# MCU.net
KiCad netlist of a schematic drawn in Altium Designer
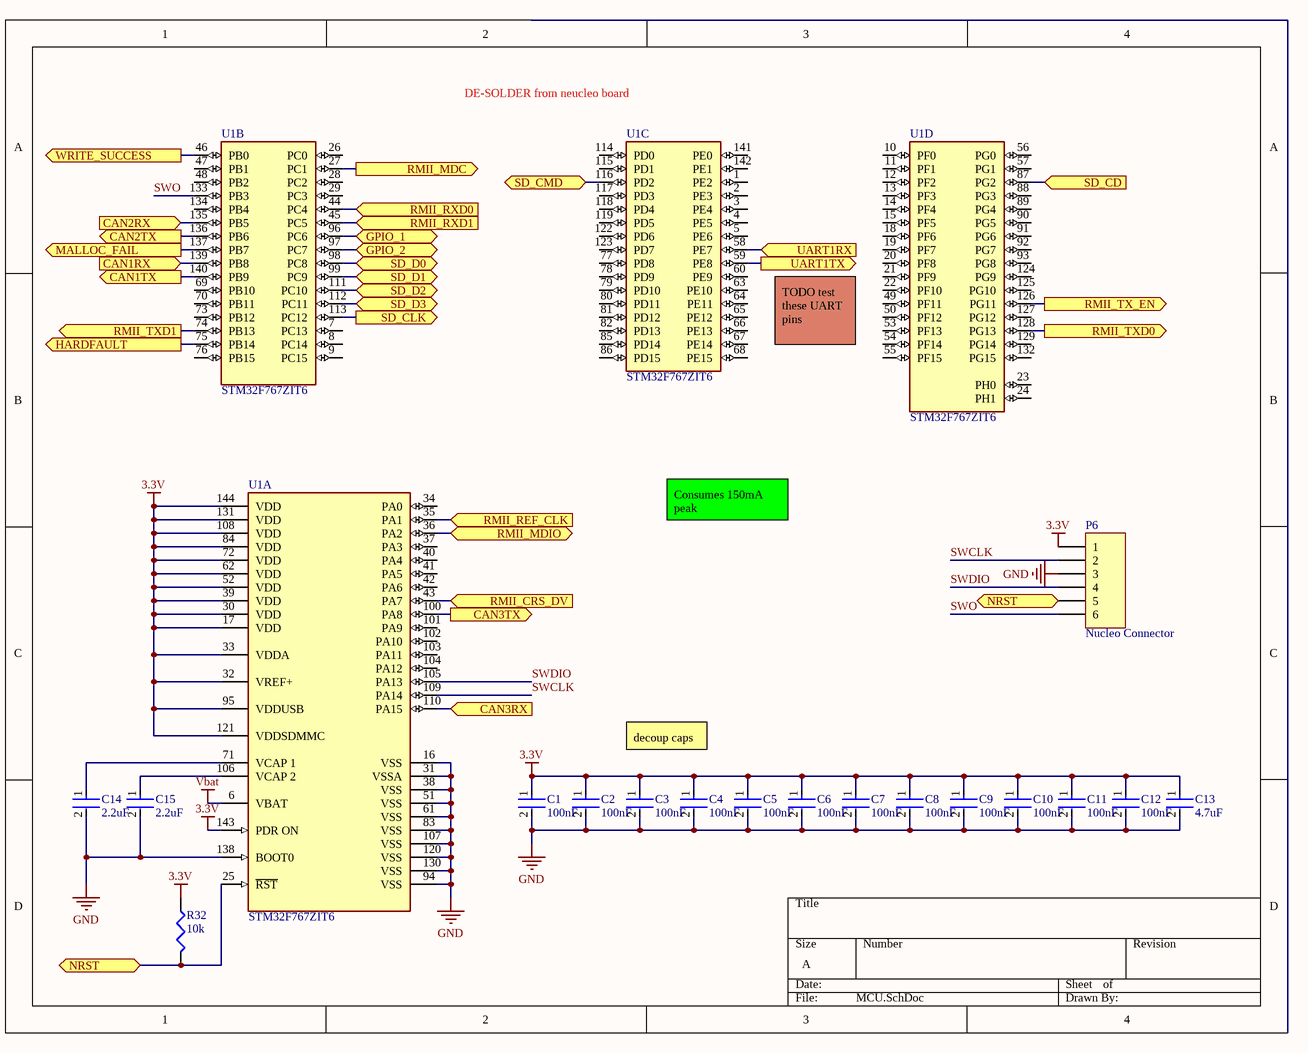
[diagram p0: MCU.SchDoc]

(export (version "E")
  (design (tool "Eeschema 10.0.6"))
  (components
    (comp (ref "C1")
      (value "100nF")
      (footprint "FP-C0603C-CF-MFG")
      (description "Any 0603 Cap is fine here")
      (fields (field (name "TOLERANCE") "0.1") (field (name "MANUFACTURER") "KEMET"))
      (libsource (lib "Altium Content Vault") (part "b4654b650e69147ec39a6b967a45e02"))
    )
    (comp (ref "C2")
      (value "100nF")
      (footprint "FP-C0603C-CF-MFG")
      (description "Any 0603 Cap is fine here")
      (fields (field (name "TOLERANCE") "0.1") (field (name "MANUFACTURER") "KEMET"))
      (libsource (lib "Altium Content Vault") (part "b4654b650e69147ec39a6b967a45e02"))
    )
    (comp (ref "C3")
      (value "100nF")
      (footprint "FP-C0603C-CF-MFG")
      (description "Any 0603 Cap is fine here")
      (fields (field (name "TOLERANCE") "0.1") (field (name "MANUFACTURER") "KEMET"))
      (libsource (lib "Altium Content Vault") (part "b4654b650e69147ec39a6b967a45e02"))
    )
    (comp (ref "C4")
      (value "100nF")
      (footprint "FP-C0603C-CF-MFG")
      (description "Any 0603 Cap is fine here")
      (fields (field (name "TOLERANCE") "0.1") (field (name "MANUFACTURER") "KEMET"))
      (libsource (lib "Altium Content Vault") (part "b4654b650e69147ec39a6b967a45e02"))
    )
    (comp (ref "C5")
      (value "100nF")
      (footprint "FP-C0603C-CF-MFG")
      (description "Any 0603 Cap is fine here")
      (fields (field (name "TOLERANCE") "0.1") (field (name "MANUFACTURER") "KEMET"))
      (libsource (lib "Altium Content Vault") (part "b4654b650e69147ec39a6b967a45e02"))
    )
    (comp (ref "C6")
      (value "100nF")
      (footprint "FP-C0603C-CF-MFG")
      (description "Any 0603 Cap is fine here")
      (fields (field (name "TOLERANCE") "0.1") (field (name "MANUFACTURER") "KEMET"))
      (libsource (lib "Altium Content Vault") (part "b4654b650e69147ec39a6b967a45e02"))
    )
    (comp (ref "C7")
      (value "100nF")
      (footprint "FP-C0603C-CF-MFG")
      (description "Any 0603 Cap is fine here")
      (fields (field (name "TOLERANCE") "0.1") (field (name "MANUFACTURER") "KEMET"))
      (libsource (lib "Altium Content Vault") (part "b4654b650e69147ec39a6b967a45e02"))
    )
    (comp (ref "C8")
      (value "100nF")
      (footprint "FP-C0603C-CF-MFG")
      (description "Any 0603 Cap is fine here")
      (fields (field (name "TOLERANCE") "0.1") (field (name "MANUFACTURER") "KEMET"))
      (libsource (lib "Altium Content Vault") (part "b4654b650e69147ec39a6b967a45e02"))
    )
    (comp (ref "C9")
      (value "100nF")
      (footprint "FP-C0603C-CF-MFG")
      (description "Any 0603 Cap is fine here")
      (fields (field (name "TOLERANCE") "0.1") (field (name "MANUFACTURER") "KEMET"))
      (libsource (lib "Altium Content Vault") (part "b4654b650e69147ec39a6b967a45e02"))
    )
    (comp (ref "C10")
      (value "100nF")
      (footprint "FP-C0603C-CF-MFG")
      (description "Any 0603 Cap is fine here")
      (fields (field (name "TOLERANCE") "0.1") (field (name "MANUFACTURER") "KEMET"))
      (libsource (lib "Altium Content Vault") (part "b4654b650e69147ec39a6b967a45e02"))
    )
    (comp (ref "C11")
      (value "100nF")
      (footprint "FP-C0603C-CF-MFG")
      (description "Any 0603 Cap is fine here")
      (fields (field (name "TOLERANCE") "0.1") (field (name "MANUFACTURER") "KEMET"))
      (libsource (lib "Altium Content Vault") (part "b4654b650e69147ec39a6b967a45e02"))
    )
    (comp (ref "C12")
      (value "100nF")
      (footprint "FP-C0603C-CF-MFG")
      (description "Any 0603 Cap is fine here")
      (fields (field (name "TOLERANCE") "0.1") (field (name "MANUFACTURER") "KEMET"))
      (libsource (lib "Altium Content Vault") (part "b4654b650e69147ec39a6b967a45e02"))
    )
    (comp (ref "C13")
      (value "4.7uF")
      (footprint "FP-C0603C-CF-MFG")
      (description "Any 0603 Cap is fine here")
      (fields (field (name "TOLERANCE") "0.1") (field (name "MANUFACTURER") "KEMET"))
      (libsource (lib "Altium Content Vault") (part "b4654b650e69147ec39a6b967a45e02"))
    )
    (comp (ref "C14")
      (value "2.2uF")
      (footprint "FP-C0603C-CF-MFG")
      (description "Any 0603 Cap is fine here")
      (fields (field (name "TOLERANCE") "0.1") (field (name "MANUFACTURER") "KEMET"))
      (libsource (lib "Altium Content Vault") (part "b4654b650e69147ec39a6b967a45e02"))
    )
    (comp (ref "C15")
      (value "2.2uF")
      (footprint "FP-C0603C-CF-MFG")
      (description "Any 0603 Cap is fine here")
      (fields (field (name "TOLERANCE") "0.1") (field (name "MANUFACTURER") "KEMET"))
      (libsource (lib "Altium Content Vault") (part "b4654b650e69147ec39a6b967a45e02"))
    )
    (comp (ref "P6")
      (value "Nucleo Connector")
      (footprint "HDR1X6")
      (description "Header, 6-Pin")
      (fields (field (name "PUBLISHER") "Altium Limited"))
      (libsource (lib "Miscellaneous Connectors") (part "Header 6"))
    )
    (comp (ref "R32")
      (value "10k")
      (footprint "J1-0603")
      (description "Resistor")
      (fields (field (name "PUBLISHER") "Altium Limited"))
      (libsource (lib "Miscellaneous Devices") (part "Res3"))
    )
    (comp (ref "U1")
      (value "STM32F767ZIT6")
      (footprint "FP-LQFP144-1A-MFG")
      (description "IC MCU 32BIT 2MB FLASH 144LQFP")
      (fields
        (field (name "OCTOPART") "https://octopart.com/stm32f767zit6-stmicroelectronics-70527068")
        (field (name "MANUFACTURER") "STMicroelectronics")
      )
      (libsource (lib "Altium Content Vault") (part "5045e889cff10565096e715f5715cbd"))
    )
  )
  (nets
    (net (code "1") (name "/CAN1RX") (class "Default")
      (node (ref "U1") (pin "139") (pinfunction "PB8_139") (pintype "bidirectional"))
    )
    (net (code "2") (name "/CAN1TX") (class "Default")
      (node (ref "U1") (pin "140") (pinfunction "PB9_140") (pintype "bidirectional"))
    )
    (net (code "3") (name "/CAN2RX") (class "Default")
      (node (ref "U1") (pin "135") (pinfunction "PB5_135") (pintype "bidirectional"))
    )
    (net (code "4") (name "/CAN2TX") (class "Default")
      (node (ref "U1") (pin "136") (pinfunction "PB6_136") (pintype "bidirectional"))
    )
    (net (code "5") (name "/CAN3RX") (class "Default")
      (node (ref "U1") (pin "110") (pinfunction "PA15_110") (pintype "bidirectional"))
    )
    (net (code "6") (name "/CAN3TX") (class "Default")
      (node (ref "U1") (pin "100") (pinfunction "PA8_100") (pintype "bidirectional"))
    )
    (net (code "7") (name "/GPIO_1") (class "Default")
      (node (ref "U1") (pin "96") (pinfunction "PC6_96") (pintype "bidirectional"))
    )
    (net (code "8") (name "/GPIO_2") (class "Default")
      (node (ref "U1") (pin "97") (pinfunction "PC7_97") (pintype "bidirectional"))
    )
    (net (code "9") (name "/HARDFAULT") (class "Default")
      (node (ref "U1") (pin "75") (pinfunction "PB14_75") (pintype "bidirectional"))
    )
    (net (code "10") (name "/MALLOC_FAIL") (class "Default")
      (node (ref "U1") (pin "137") (pinfunction "PB7_137") (pintype "bidirectional"))
    )
    (net (code "11") (name "/NRST") (class "Default")
      (node (ref "P6") (pin "5") (pinfunction "5_5") (pintype "passive"))
      (node (ref "R32") (pin "2") (pinfunction "2_2") (pintype "passive"))
      (node (ref "U1") (pin "25") (pinfunction "~{RST}_25") (pintype "input"))
    )
    (net (code "12") (name "/RMII_CRS_DV") (class "Default")
      (node (ref "U1") (pin "43") (pinfunction "PA7_43") (pintype "bidirectional"))
    )
    (net (code "13") (name "/RMII_MDC") (class "Default")
      (node (ref "U1") (pin "27") (pinfunction "PC1_27") (pintype "bidirectional"))
    )
    (net (code "14") (name "/RMII_MDIO") (class "Default")
      (node (ref "U1") (pin "36") (pinfunction "PA2_36") (pintype "bidirectional"))
    )
    (net (code "15") (name "/RMII_REF_CLK") (class "Default")
      (node (ref "U1") (pin "35") (pinfunction "PA1_35") (pintype "bidirectional"))
    )
    (net (code "16") (name "/RMII_RXD0") (class "Default")
      (node (ref "U1") (pin "44") (pinfunction "PC4_44") (pintype "bidirectional"))
    )
    (net (code "17") (name "/RMII_RXD1") (class "Default")
      (node (ref "U1") (pin "45") (pinfunction "PC5_45") (pintype "bidirectional"))
    )
    (net (code "18") (name "/RMII_TXD0") (class "Default")
      (node (ref "U1") (pin "128") (pinfunction "PG13_128") (pintype "bidirectional"))
    )
    (net (code "19") (name "/RMII_TXD1") (class "Default")
      (node (ref "U1") (pin "74") (pinfunction "PB13_74") (pintype "bidirectional"))
    )
    (net (code "20") (name "/RMII_TX_EN") (class "Default")
      (node (ref "U1") (pin "126") (pinfunction "PG11_126") (pintype "bidirectional"))
    )
    (net (code "21") (name "/SD_CD") (class "Default")
      (node (ref "U1") (pin "87") (pinfunction "PG2_87") (pintype "bidirectional"))
    )
    (net (code "22") (name "/SD_CLK") (class "Default")
      (node (ref "U1") (pin "113") (pinfunction "PC12_113") (pintype "bidirectional"))
    )
    (net (code "23") (name "/SD_CMD") (class "Default")
      (node (ref "U1") (pin "116") (pinfunction "PD2_116") (pintype "bidirectional"))
    )
    (net (code "24") (name "/SD_D0") (class "Default")
      (node (ref "U1") (pin "98") (pinfunction "PC8_98") (pintype "bidirectional"))
    )
    (net (code "25") (name "/SD_D1") (class "Default")
      (node (ref "U1") (pin "99") (pinfunction "PC9_99") (pintype "bidirectional"))
    )
    (net (code "26") (name "/SD_D2") (class "Default")
      (node (ref "U1") (pin "111") (pinfunction "PC10_111") (pintype "bidirectional"))
    )
    (net (code "27") (name "/SD_D3") (class "Default")
      (node (ref "U1") (pin "112") (pinfunction "PC11_112") (pintype "bidirectional"))
    )
    (net (code "28") (name "/SWCLK") (class "Default")
      (node (ref "P6") (pin "2") (pinfunction "2_2") (pintype "passive"))
      (node (ref "U1") (pin "109") (pinfunction "PA14_109") (pintype "bidirectional"))
    )
    (net (code "29") (name "/SWDIO") (class "Default")
      (node (ref "P6") (pin "4") (pinfunction "4_4") (pintype "passive"))
      (node (ref "U1") (pin "105") (pinfunction "PA13_105") (pintype "bidirectional"))
    )
    (net (code "30") (name "/SWO") (class "Default")
      (node (ref "P6") (pin "6") (pinfunction "6_6") (pintype "passive"))
      (node (ref "U1") (pin "133") (pinfunction "PB3_133") (pintype "bidirectional"))
    )
    (net (code "31") (name "/UART1RX") (class "Default")
      (node (ref "U1") (pin "58") (pinfunction "PE7_58") (pintype "bidirectional"))
    )
    (net (code "32") (name "/UART1TX") (class "Default")
      (node (ref "U1") (pin "59") (pinfunction "PE8_59") (pintype "bidirectional"))
    )
    (net (code "33") (name "/WRITE_SUCCESS") (class "Default")
      (node (ref "U1") (pin "46") (pinfunction "PB0_46") (pintype "bidirectional"))
    )
    (net (code "34") (name "3.3V") (class "Default")
      (node (ref "C1") (pin "1") (pinfunction "1_1") (pintype "passive"))
      (node (ref "C10") (pin "1") (pinfunction "1_1") (pintype "passive"))
      (node (ref "C11") (pin "1") (pinfunction "1_1") (pintype "passive"))
      (node (ref "C12") (pin "1") (pinfunction "1_1") (pintype "passive"))
      (node (ref "C13") (pin "1") (pinfunction "1_1") (pintype "passive"))
      (node (ref "C2") (pin "1") (pinfunction "1_1") (pintype "passive"))
      (node (ref "C3") (pin "1") (pinfunction "1_1") (pintype "passive"))
      (node (ref "C4") (pin "1") (pinfunction "1_1") (pintype "passive"))
      (node (ref "C5") (pin "1") (pinfunction "1_1") (pintype "passive"))
      (node (ref "C6") (pin "1") (pinfunction "1_1") (pintype "passive"))
      (node (ref "C7") (pin "1") (pinfunction "1_1") (pintype "passive"))
      (node (ref "C8") (pin "1") (pinfunction "1_1") (pintype "passive"))
      (node (ref "C9") (pin "1") (pinfunction "1_1") (pintype "passive"))
      (node (ref "P6") (pin "1") (pinfunction "1_1") (pintype "passive"))
      (node (ref "R32") (pin "1") (pinfunction "1_1") (pintype "passive"))
      (node (ref "U1") (pin "108") (pinfunction "VDD_108") (pintype "power_in"))
      (node (ref "U1") (pin "121") (pinfunction "VDDSDMMC_121") (pintype "power_in"))
      (node (ref "U1") (pin "131") (pinfunction "VDD_131") (pintype "power_in"))
      (node (ref "U1") (pin "143") (pinfunction "PDR_ON_143") (pintype "input"))
      (node (ref "U1") (pin "144") (pinfunction "VDD_144") (pintype "power_in"))
      (node (ref "U1") (pin "17") (pinfunction "VDD_17") (pintype "power_in"))
      (node (ref "U1") (pin "30") (pinfunction "VDD_30") (pintype "power_in"))
      (node (ref "U1") (pin "32") (pinfunction "VREF+_32") (pintype "power_in"))
      (node (ref "U1") (pin "33") (pinfunction "VDDA_33") (pintype "power_in"))
      (node (ref "U1") (pin "39") (pinfunction "VDD_39") (pintype "power_in"))
      (node (ref "U1") (pin "52") (pinfunction "VDD_52") (pintype "power_in"))
      (node (ref "U1") (pin "62") (pinfunction "VDD_62") (pintype "power_in"))
      (node (ref "U1") (pin "72") (pinfunction "VDD_72") (pintype "power_in"))
      (node (ref "U1") (pin "84") (pinfunction "VDD_84") (pintype "power_in"))
      (node (ref "U1") (pin "95") (pinfunction "VDDUSB_95") (pintype "power_in"))
    )
    (net (code "35") (name "GND") (class "Default")
      (node (ref "C1") (pin "2") (pinfunction "2_2") (pintype "passive"))
      (node (ref "C10") (pin "2") (pinfunction "2_2") (pintype "passive"))
      (node (ref "C11") (pin "2") (pinfunction "2_2") (pintype "passive"))
      (node (ref "C12") (pin "2") (pinfunction "2_2") (pintype "passive"))
      (node (ref "C13") (pin "2") (pinfunction "2_2") (pintype "passive"))
      (node (ref "C14") (pin "2") (pinfunction "2_2") (pintype "passive"))
      (node (ref "C15") (pin "2") (pinfunction "2_2") (pintype "passive"))
      (node (ref "C2") (pin "2") (pinfunction "2_2") (pintype "passive"))
      (node (ref "C3") (pin "2") (pinfunction "2_2") (pintype "passive"))
      (node (ref "C4") (pin "2") (pinfunction "2_2") (pintype "passive"))
      (node (ref "C5") (pin "2") (pinfunction "2_2") (pintype "passive"))
      (node (ref "C6") (pin "2") (pinfunction "2_2") (pintype "passive"))
      (node (ref "C7") (pin "2") (pinfunction "2_2") (pintype "passive"))
      (node (ref "C8") (pin "2") (pinfunction "2_2") (pintype "passive"))
      (node (ref "C9") (pin "2") (pinfunction "2_2") (pintype "passive"))
      (node (ref "P6") (pin "3") (pinfunction "3_3") (pintype "passive"))
      (node (ref "U1") (pin "107") (pinfunction "VSS_107") (pintype "power_in"))
      (node (ref "U1") (pin "120") (pinfunction "VSS_120") (pintype "power_in"))
      (node (ref "U1") (pin "130") (pinfunction "VSS_130") (pintype "power_in"))
      (node (ref "U1") (pin "138") (pinfunction "BOOT0_138") (pintype "input"))
      (node (ref "U1") (pin "16") (pinfunction "VSS_16") (pintype "power_in"))
      (node (ref "U1") (pin "31") (pinfunction "VSSA_31") (pintype "power_in"))
      (node (ref "U1") (pin "38") (pinfunction "VSS_38") (pintype "power_in"))
      (node (ref "U1") (pin "51") (pinfunction "VSS_51") (pintype "power_in"))
      (node (ref "U1") (pin "61") (pinfunction "VSS_61") (pintype "power_in"))
      (node (ref "U1") (pin "83") (pinfunction "VSS_83") (pintype "power_in"))
      (node (ref "U1") (pin "94") (pinfunction "VSS_94") (pintype "power_in"))
    )
    (net (code "36") (name "Net-(U1A-VCAP_1)") (class "Default")
      (node (ref "C14") (pin "1") (pinfunction "1_1") (pintype "passive"))
      (node (ref "U1") (pin "71") (pinfunction "VCAP_1_71") (pintype "power_in"))
    )
    (net (code "37") (name "Net-(U1A-VCAP_2)") (class "Default")
      (node (ref "C15") (pin "1") (pinfunction "1_1") (pintype "passive"))
      (node (ref "U1") (pin "106") (pinfunction "VCAP_2_106") (pintype "power_in"))
    )
    (net (code "38") (name "Vbat") (class "Default")
      (node (ref "U1") (pin "6") (pinfunction "VBAT_6") (pintype "power_in"))
    )
    (net (code "39") (name "unconnected-(U1A-PA0-Pad34)") (class "Default")
      (node (ref "U1") (pin "34") (pinfunction "PA0_34") (pintype "bidirectional"))
    )
    (net (code "40") (name "unconnected-(U1A-PA3-Pad37)") (class "Default")
      (node (ref "U1") (pin "37") (pinfunction "PA3_37") (pintype "bidirectional"))
    )
    (net (code "41") (name "unconnected-(U1A-PA4-Pad40)") (class "Default")
      (node (ref "U1") (pin "40") (pinfunction "PA4_40") (pintype "bidirectional"))
    )
    (net (code "42") (name "unconnected-(U1A-PA5-Pad41)") (class "Default")
      (node (ref "U1") (pin "41") (pinfunction "PA5_41") (pintype "bidirectional"))
    )
    (net (code "43") (name "unconnected-(U1A-PA6-Pad42)") (class "Default")
      (node (ref "U1") (pin "42") (pinfunction "PA6_42") (pintype "bidirectional"))
    )
    (net (code "44") (name "unconnected-(U1A-PA9-Pad101)") (class "Default")
      (node (ref "U1") (pin "101") (pinfunction "PA9_101") (pintype "bidirectional"))
    )
    (net (code "45") (name "unconnected-(U1A-PA10-Pad102)") (class "Default")
      (node (ref "U1") (pin "102") (pinfunction "PA10_102") (pintype "bidirectional"))
    )
    (net (code "46") (name "unconnected-(U1A-PA11-Pad103)") (class "Default")
      (node (ref "U1") (pin "103") (pinfunction "PA11_103") (pintype "bidirectional"))
    )
    (net (code "47") (name "unconnected-(U1A-PA12-Pad104)") (class "Default")
      (node (ref "U1") (pin "104") (pinfunction "PA12_104") (pintype "bidirectional"))
    )
    (net (code "48") (name "unconnected-(U1B-PB1-Pad47)") (class "Default")
      (node (ref "U1") (pin "47") (pinfunction "PB1_47") (pintype "bidirectional"))
    )
    (net (code "49") (name "unconnected-(U1B-PB2-Pad48)") (class "Default")
      (node (ref "U1") (pin "48") (pinfunction "PB2_48") (pintype "bidirectional"))
    )
    (net (code "50") (name "unconnected-(U1B-PB4-Pad134)") (class "Default")
      (node (ref "U1") (pin "134") (pinfunction "PB4_134") (pintype "bidirectional"))
    )
    (net (code "51") (name "unconnected-(U1B-PB10-Pad69)") (class "Default")
      (node (ref "U1") (pin "69") (pinfunction "PB10_69") (pintype "bidirectional"))
    )
    (net (code "52") (name "unconnected-(U1B-PB11-Pad70)") (class "Default")
      (node (ref "U1") (pin "70") (pinfunction "PB11_70") (pintype "bidirectional"))
    )
    (net (code "53") (name "unconnected-(U1B-PB12-Pad73)") (class "Default")
      (node (ref "U1") (pin "73") (pinfunction "PB12_73") (pintype "bidirectional"))
    )
    (net (code "54") (name "unconnected-(U1B-PB15-Pad76)") (class "Default")
      (node (ref "U1") (pin "76") (pinfunction "PB15_76") (pintype "bidirectional"))
    )
    (net (code "55") (name "unconnected-(U1B-PC0-Pad26)") (class "Default")
      (node (ref "U1") (pin "26") (pinfunction "PC0_26") (pintype "bidirectional"))
    )
    (net (code "56") (name "unconnected-(U1B-PC2-Pad28)") (class "Default")
      (node (ref "U1") (pin "28") (pinfunction "PC2_28") (pintype "bidirectional"))
    )
    (net (code "57") (name "unconnected-(U1B-PC3-Pad29)") (class "Default")
      (node (ref "U1") (pin "29") (pinfunction "PC3_29") (pintype "bidirectional"))
    )
    (net (code "58") (name "unconnected-(U1B-PC13-Pad7)") (class "Default")
      (node (ref "U1") (pin "7") (pinfunction "PC13_7") (pintype "bidirectional"))
    )
    (net (code "59") (name "unconnected-(U1B-PC14-Pad8)") (class "Default")
      (node (ref "U1") (pin "8") (pinfunction "PC14_8") (pintype "bidirectional"))
    )
    (net (code "60") (name "unconnected-(U1B-PC15-Pad9)") (class "Default")
      (node (ref "U1") (pin "9") (pinfunction "PC15_9") (pintype "bidirectional"))
    )
    (net (code "61") (name "unconnected-(U1C-PD0-Pad114)") (class "Default")
      (node (ref "U1") (pin "114") (pinfunction "PD0_114") (pintype "bidirectional"))
    )
    (net (code "62") (name "unconnected-(U1C-PD1-Pad115)") (class "Default")
      (node (ref "U1") (pin "115") (pinfunction "PD1_115") (pintype "bidirectional"))
    )
    (net (code "63") (name "unconnected-(U1C-PD3-Pad117)") (class "Default")
      (node (ref "U1") (pin "117") (pinfunction "PD3_117") (pintype "bidirectional"))
    )
    (net (code "64") (name "unconnected-(U1C-PD4-Pad118)") (class "Default")
      (node (ref "U1") (pin "118") (pinfunction "PD4_118") (pintype "bidirectional"))
    )
    (net (code "65") (name "unconnected-(U1C-PD5-Pad119)") (class "Default")
      (node (ref "U1") (pin "119") (pinfunction "PD5_119") (pintype "bidirectional"))
    )
    (net (code "66") (name "unconnected-(U1C-PD6-Pad122)") (class "Default")
      (node (ref "U1") (pin "122") (pinfunction "PD6_122") (pintype "bidirectional"))
    )
    (net (code "67") (name "unconnected-(U1C-PD7-Pad123)") (class "Default")
      (node (ref "U1") (pin "123") (pinfunction "PD7_123") (pintype "bidirectional"))
    )
    (net (code "68") (name "unconnected-(U1C-PD8-Pad77)") (class "Default")
      (node (ref "U1") (pin "77") (pinfunction "PD8_77") (pintype "bidirectional"))
    )
    (net (code "69") (name "unconnected-(U1C-PD9-Pad78)") (class "Default")
      (node (ref "U1") (pin "78") (pinfunction "PD9_78") (pintype "bidirectional"))
    )
    (net (code "70") (name "unconnected-(U1C-PD10-Pad79)") (class "Default")
      (node (ref "U1") (pin "79") (pinfunction "PD10_79") (pintype "bidirectional"))
    )
    (net (code "71") (name "unconnected-(U1C-PD11-Pad80)") (class "Default")
      (node (ref "U1") (pin "80") (pinfunction "PD11_80") (pintype "bidirectional"))
    )
    (net (code "72") (name "unconnected-(U1C-PD12-Pad81)") (class "Default")
      (node (ref "U1") (pin "81") (pinfunction "PD12_81") (pintype "bidirectional"))
    )
    (net (code "73") (name "unconnected-(U1C-PD13-Pad82)") (class "Default")
      (node (ref "U1") (pin "82") (pinfunction "PD13_82") (pintype "bidirectional"))
    )
    (net (code "74") (name "unconnected-(U1C-PD14-Pad85)") (class "Default")
      (node (ref "U1") (pin "85") (pinfunction "PD14_85") (pintype "bidirectional"))
    )
    (net (code "75") (name "unconnected-(U1C-PD15-Pad86)") (class "Default")
      (node (ref "U1") (pin "86") (pinfunction "PD15_86") (pintype "bidirectional"))
    )
    (net (code "76") (name "unconnected-(U1C-PE0-Pad141)") (class "Default")
      (node (ref "U1") (pin "141") (pinfunction "PE0_141") (pintype "bidirectional"))
    )
    (net (code "77") (name "unconnected-(U1C-PE1-Pad142)") (class "Default")
      (node (ref "U1") (pin "142") (pinfunction "PE1_142") (pintype "bidirectional"))
    )
    (net (code "78") (name "unconnected-(U1C-PE2-Pad1)") (class "Default")
      (node (ref "U1") (pin "1") (pinfunction "PE2_1") (pintype "bidirectional"))
    )
    (net (code "79") (name "unconnected-(U1C-PE3-Pad2)") (class "Default")
      (node (ref "U1") (pin "2") (pinfunction "PE3_2") (pintype "bidirectional"))
    )
    (net (code "80") (name "unconnected-(U1C-PE4-Pad3)") (class "Default")
      (node (ref "U1") (pin "3") (pinfunction "PE4_3") (pintype "bidirectional"))
    )
    (net (code "81") (name "unconnected-(U1C-PE5-Pad4)") (class "Default")
      (node (ref "U1") (pin "4") (pinfunction "PE5_4") (pintype "bidirectional"))
    )
    (net (code "82") (name "unconnected-(U1C-PE6-Pad5)") (class "Default")
      (node (ref "U1") (pin "5") (pinfunction "PE6_5") (pintype "bidirectional"))
    )
    (net (code "83") (name "unconnected-(U1C-PE9-Pad60)") (class "Default")
      (node (ref "U1") (pin "60") (pinfunction "PE9_60") (pintype "bidirectional"))
    )
    (net (code "84") (name "unconnected-(U1C-PE10-Pad63)") (class "Default")
      (node (ref "U1") (pin "63") (pinfunction "PE10_63") (pintype "bidirectional"))
    )
    (net (code "85") (name "unconnected-(U1C-PE11-Pad64)") (class "Default")
      (node (ref "U1") (pin "64") (pinfunction "PE11_64") (pintype "bidirectional"))
    )
    (net (code "86") (name "unconnected-(U1C-PE12-Pad65)") (class "Default")
      (node (ref "U1") (pin "65") (pinfunction "PE12_65") (pintype "bidirectional"))
    )
    (net (code "87") (name "unconnected-(U1C-PE13-Pad66)") (class "Default")
      (node (ref "U1") (pin "66") (pinfunction "PE13_66") (pintype "bidirectional"))
    )
    (net (code "88") (name "unconnected-(U1C-PE14-Pad67)") (class "Default")
      (node (ref "U1") (pin "67") (pinfunction "PE14_67") (pintype "bidirectional"))
    )
    (net (code "89") (name "unconnected-(U1C-PE15-Pad68)") (class "Default")
      (node (ref "U1") (pin "68") (pinfunction "PE15_68") (pintype "bidirectional"))
    )
    (net (code "90") (name "unconnected-(U1D-PF0-Pad10)") (class "Default")
      (node (ref "U1") (pin "10") (pinfunction "PF0_10") (pintype "bidirectional"))
    )
    (net (code "91") (name "unconnected-(U1D-PF1-Pad11)") (class "Default")
      (node (ref "U1") (pin "11") (pinfunction "PF1_11") (pintype "bidirectional"))
    )
    (net (code "92") (name "unconnected-(U1D-PF2-Pad12)") (class "Default")
      (node (ref "U1") (pin "12") (pinfunction "PF2_12") (pintype "bidirectional"))
    )
    (net (code "93") (name "unconnected-(U1D-PF3-Pad13)") (class "Default")
      (node (ref "U1") (pin "13") (pinfunction "PF3_13") (pintype "bidirectional"))
    )
    (net (code "94") (name "unconnected-(U1D-PF4-Pad14)") (class "Default")
      (node (ref "U1") (pin "14") (pinfunction "PF4_14") (pintype "bidirectional"))
    )
    (net (code "95") (name "unconnected-(U1D-PF5-Pad15)") (class "Default")
      (node (ref "U1") (pin "15") (pinfunction "PF5_15") (pintype "bidirectional"))
    )
    (net (code "96") (name "unconnected-(U1D-PF6-Pad18)") (class "Default")
      (node (ref "U1") (pin "18") (pinfunction "PF6_18") (pintype "bidirectional"))
    )
    (net (code "97") (name "unconnected-(U1D-PF7-Pad19)") (class "Default")
      (node (ref "U1") (pin "19") (pinfunction "PF7_19") (pintype "bidirectional"))
    )
    (net (code "98") (name "unconnected-(U1D-PF8-Pad20)") (class "Default")
      (node (ref "U1") (pin "20") (pinfunction "PF8_20") (pintype "bidirectional"))
    )
    (net (code "99") (name "unconnected-(U1D-PF9-Pad21)") (class "Default")
      (node (ref "U1") (pin "21") (pinfunction "PF9_21") (pintype "bidirectional"))
    )
    (net (code "100") (name "unconnected-(U1D-PF10-Pad22)") (class "Default")
      (node (ref "U1") (pin "22") (pinfunction "PF10_22") (pintype "bidirectional"))
    )
    (net (code "101") (name "unconnected-(U1D-PF11-Pad49)") (class "Default")
      (node (ref "U1") (pin "49") (pinfunction "PF11_49") (pintype "bidirectional"))
    )
    (net (code "102") (name "unconnected-(U1D-PF12-Pad50)") (class "Default")
      (node (ref "U1") (pin "50") (pinfunction "PF12_50") (pintype "bidirectional"))
    )
    (net (code "103") (name "unconnected-(U1D-PF13-Pad53)") (class "Default")
      (node (ref "U1") (pin "53") (pinfunction "PF13_53") (pintype "bidirectional"))
    )
    (net (code "104") (name "unconnected-(U1D-PF14-Pad54)") (class "Default")
      (node (ref "U1") (pin "54") (pinfunction "PF14_54") (pintype "bidirectional"))
    )
    (net (code "105") (name "unconnected-(U1D-PF15-Pad55)") (class "Default")
      (node (ref "U1") (pin "55") (pinfunction "PF15_55") (pintype "bidirectional"))
    )
    (net (code "106") (name "unconnected-(U1D-PG0-Pad56)") (class "Default")
      (node (ref "U1") (pin "56") (pinfunction "PG0_56") (pintype "bidirectional"))
    )
    (net (code "107") (name "unconnected-(U1D-PG1-Pad57)") (class "Default")
      (node (ref "U1") (pin "57") (pinfunction "PG1_57") (pintype "bidirectional"))
    )
    (net (code "108") (name "unconnected-(U1D-PG3-Pad88)") (class "Default")
      (node (ref "U1") (pin "88") (pinfunction "PG3_88") (pintype "bidirectional"))
    )
    (net (code "109") (name "unconnected-(U1D-PG4-Pad89)") (class "Default")
      (node (ref "U1") (pin "89") (pinfunction "PG4_89") (pintype "bidirectional"))
    )
    (net (code "110") (name "unconnected-(U1D-PG5-Pad90)") (class "Default")
      (node (ref "U1") (pin "90") (pinfunction "PG5_90") (pintype "bidirectional"))
    )
    (net (code "111") (name "unconnected-(U1D-PG6-Pad91)") (class "Default")
      (node (ref "U1") (pin "91") (pinfunction "PG6_91") (pintype "bidirectional"))
    )
    (net (code "112") (name "unconnected-(U1D-PG7-Pad92)") (class "Default")
      (node (ref "U1") (pin "92") (pinfunction "PG7_92") (pintype "bidirectional"))
    )
    (net (code "113") (name "unconnected-(U1D-PG8-Pad93)") (class "Default")
      (node (ref "U1") (pin "93") (pinfunction "PG8_93") (pintype "bidirectional"))
    )
    (net (code "114") (name "unconnected-(U1D-PG9-Pad124)") (class "Default")
      (node (ref "U1") (pin "124") (pinfunction "PG9_124") (pintype "bidirectional"))
    )
    (net (code "115") (name "unconnected-(U1D-PG10-Pad125)") (class "Default")
      (node (ref "U1") (pin "125") (pinfunction "PG10_125") (pintype "bidirectional"))
    )
    (net (code "116") (name "unconnected-(U1D-PG12-Pad127)") (class "Default")
      (node (ref "U1") (pin "127") (pinfunction "PG12_127") (pintype "bidirectional"))
    )
    (net (code "117") (name "unconnected-(U1D-PG14-Pad129)") (class "Default")
      (node (ref "U1") (pin "129") (pinfunction "PG14_129") (pintype "bidirectional"))
    )
    (net (code "118") (name "unconnected-(U1D-PG15-Pad132)") (class "Default")
      (node (ref "U1") (pin "132") (pinfunction "PG15_132") (pintype "bidirectional"))
    )
    (net (code "119") (name "unconnected-(U1D-PH0-Pad23)") (class "Default")
      (node (ref "U1") (pin "23") (pinfunction "PH0_23") (pintype "bidirectional"))
    )
    (net (code "120") (name "unconnected-(U1D-PH1-Pad24)") (class "Default")
      (node (ref "U1") (pin "24") (pinfunction "PH1_24") (pintype "bidirectional"))
    )
  )
)
